# ina.net
KiCad netlist of a schematic drawn in EAGLE
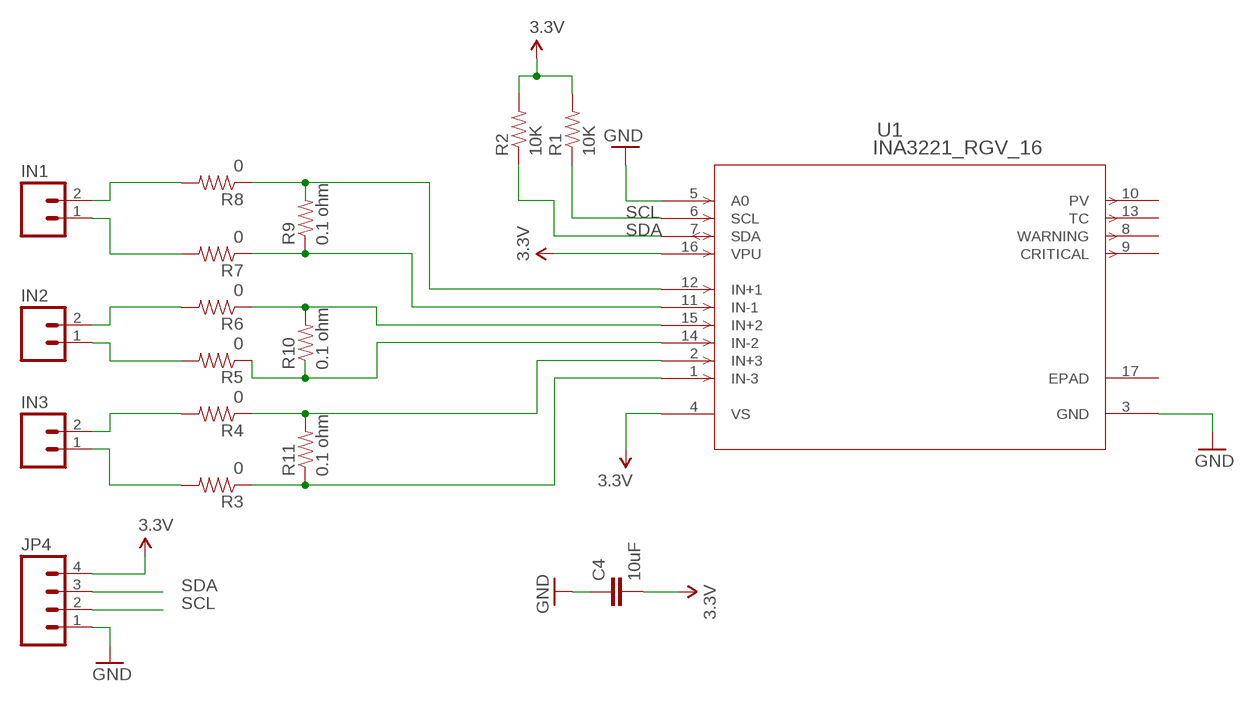
[diagram p0: schematic, sheet 1]

(export (version "E")
  (design (tool "Eeschema 10.0.6"))
  (components
    (comp (ref "C4")
      (value "10uF")
      (footprint "eagle-import:1206")
      (fields (field (name "MF") "WALSIN") (field (name "MPN") "1206B106K160CT"))
      (libsource (lib "eagle-import") (part "CAP1206"))
    )
    (comp (ref "IN1")
      (value "M02PTH")
      (footprint "eagle-import:1X02")
      (libsource (lib "eagle-import") (part "M02PTH"))
    )
    (comp (ref "IN2")
      (value "M02PTH")
      (footprint "eagle-import:1X02")
      (libsource (lib "eagle-import") (part "M02PTH"))
    )
    (comp (ref "IN3")
      (value "M02PTH")
      (footprint "eagle-import:1X02")
      (libsource (lib "eagle-import") (part "M02PTH"))
    )
    (comp (ref "JP4")
      (value "M04LONGPADS")
      (footprint "eagle-import:1X04_LONGPADS")
      (libsource (lib "eagle-import") (part "M04LONGPADS"))
    )
    (comp (ref "R1")
      (value "10K")
      (footprint "eagle-import:1206")
      (fields (field (name "MF") "YAGEO (PHYCOMP)") (field (name "MPN") "RC1206FR-0710KL"))
      (libsource (lib "eagle-import") (part "RESISTOR1206"))
    )
    (comp (ref "R2")
      (value "10K")
      (footprint "eagle-import:1206")
      (fields (field (name "MF") "YAGEO (PHYCOMP)") (field (name "MPN") "RC1206FR-0710KL"))
      (libsource (lib "eagle-import") (part "RESISTOR1206"))
    )
    (comp (ref "R3")
      (value "0")
      (footprint "eagle-import:1206")
      (fields (field (name "MF") "WELWYN") (field (name "MPN") "WCR1206-R005JI"))
      (libsource (lib "eagle-import") (part "RESISTOR1206"))
    )
    (comp (ref "R4")
      (value "0")
      (footprint "eagle-import:1206")
      (fields (field (name "MF") "WELWYN") (field (name "MPN") "WCR1206-R005JI"))
      (libsource (lib "eagle-import") (part "RESISTOR1206"))
    )
    (comp (ref "R5")
      (value "0")
      (footprint "eagle-import:1206")
      (fields (field (name "MF") "WELWYN") (field (name "MPN") "WCR1206-R005JI"))
      (libsource (lib "eagle-import") (part "RESISTOR1206"))
    )
    (comp (ref "R6")
      (value "0")
      (footprint "eagle-import:1206")
      (fields (field (name "MF") "WELWYN") (field (name "MPN") "WCR1206-R005JI"))
      (libsource (lib "eagle-import") (part "RESISTOR1206"))
    )
    (comp (ref "R7")
      (value "0")
      (footprint "eagle-import:1206")
      (fields (field (name "MF") "WELWYN") (field (name "MPN") "WCR1206-R005JI"))
      (libsource (lib "eagle-import") (part "RESISTOR1206"))
    )
    (comp (ref "R8")
      (value "0")
      (footprint "eagle-import:1206")
      (fields (field (name "MF") "WELWYN") (field (name "MPN") "WCR1206-R005JI"))
      (libsource (lib "eagle-import") (part "RESISTOR1206"))
    )
    (comp (ref "R9")
      (value "0.1 ohm")
      (footprint "eagle-import:R2512")
      (fields (field (name "MF") "BOURNS") (field (name "MPN") "CRM2512-JX-R100ELF"))
      (libsource (lib "eagle-import") (part "RESISTOR2512"))
    )
    (comp (ref "R10")
      (value "0.1 ohm")
      (footprint "eagle-import:R2512")
      (fields (field (name "MF") "BOURNS") (field (name "MPN") "CRM2512-JX-R100ELF"))
      (libsource (lib "eagle-import") (part "RESISTOR2512"))
    )
    (comp (ref "R11")
      (value "0.1 ohm")
      (footprint "eagle-import:R2512")
      (fields (field (name "MF") "BOURNS") (field (name "MPN") "CRM2512-JX-R100ELF"))
      (libsource (lib "eagle-import") (part "RESISTOR2512"))
    )
    (comp (ref "U1")
      (value "INA3221_RGV_16")
      (footprint "eagle-import:RGV16_2P16X2P16")
      (fields
        (field (name "GENERIC_PART_NUMBER") "INA3221")
        (field (name "MANUFACTURER") "Texas Instruments")
        (field (name "MF") "TEXAS INSTRUMENTS")
      )
      (libsource (lib "eagle-import") (part "INA3221_RGV_16"))
    )
  )
  (nets
    (net (code "1") (name "/SCL") (class "Default")
      (node (ref "JP4") (pin "2") (pinfunction "2_2") (pintype "passive"))
      (node (ref "R1") (pin "1") (pinfunction "1_1") (pintype "passive"))
      (node (ref "U1") (pin "6") (pinfunction "SCL_6") (pintype "input"))
    )
    (net (code "2") (name "/SDA") (class "Default")
      (node (ref "JP4") (pin "3") (pinfunction "3_3") (pintype "passive"))
      (node (ref "R2") (pin "1") (pinfunction "1_1") (pintype "passive"))
      (node (ref "U1") (pin "7") (pinfunction "SDA_7") (pintype "bidirectional"))
    )
    (net (code "3") (name "3.3V") (class "Default")
      (node (ref "C4") (pin "2") (pinfunction "2_2") (pintype "passive"))
      (node (ref "JP4") (pin "4") (pinfunction "4_4") (pintype "passive"))
      (node (ref "R1") (pin "2") (pinfunction "2_2") (pintype "passive"))
      (node (ref "R2") (pin "2") (pinfunction "2_2") (pintype "passive"))
      (node (ref "U1") (pin "16") (pinfunction "VPU_16") (pintype "input"))
      (node (ref "U1") (pin "4") (pinfunction "VS_4") (pintype "passive"))
    )
    (net (code "4") (name "GND") (class "Default")
      (node (ref "C4") (pin "1") (pinfunction "1_1") (pintype "passive"))
      (node (ref "JP4") (pin "1") (pinfunction "1_1") (pintype "passive"))
      (node (ref "U1") (pin "3") (pinfunction "GND_3") (pintype "power_in"))
      (node (ref "U1") (pin "5") (pinfunction "A0_5") (pintype "input"))
    )
    (net (code "5") (name "Net-(IN1-Pad1)") (class "Default")
      (node (ref "IN1") (pin "1") (pinfunction "1_1") (pintype "passive"))
      (node (ref "R7") (pin "2") (pinfunction "2_2") (pintype "passive"))
    )
    (net (code "6") (name "Net-(IN1-Pad2)") (class "Default")
      (node (ref "IN1") (pin "2") (pinfunction "2_2") (pintype "passive"))
      (node (ref "R8") (pin "2") (pinfunction "2_2") (pintype "passive"))
    )
    (net (code "7") (name "Net-(IN2-Pad1)") (class "Default")
      (node (ref "IN2") (pin "1") (pinfunction "1_1") (pintype "passive"))
      (node (ref "R5") (pin "2") (pinfunction "2_2") (pintype "passive"))
    )
    (net (code "8") (name "Net-(IN2-Pad2)") (class "Default")
      (node (ref "IN2") (pin "2") (pinfunction "2_2") (pintype "passive"))
      (node (ref "R6") (pin "2") (pinfunction "2_2") (pintype "passive"))
    )
    (net (code "9") (name "Net-(IN3-Pad1)") (class "Default")
      (node (ref "IN3") (pin "1") (pinfunction "1_1") (pintype "passive"))
      (node (ref "R3") (pin "2") (pinfunction "2_2") (pintype "passive"))
    )
    (net (code "10") (name "Net-(IN3-Pad2)") (class "Default")
      (node (ref "IN3") (pin "2") (pinfunction "2_2") (pintype "passive"))
      (node (ref "R4") (pin "2") (pinfunction "2_2") (pintype "passive"))
    )
    (net (code "11") (name "Net-(U1-IN+1)") (class "Default")
      (node (ref "R8") (pin "1") (pinfunction "1_1") (pintype "passive"))
      (node (ref "R9") (pin "2") (pinfunction "2_2") (pintype "passive"))
      (node (ref "U1") (pin "12") (pinfunction "IN+1_12") (pintype "input"))
    )
    (net (code "12") (name "Net-(U1-IN+2)") (class "Default")
      (node (ref "R10") (pin "2") (pinfunction "2_2") (pintype "passive"))
      (node (ref "R6") (pin "1") (pinfunction "1_1") (pintype "passive"))
      (node (ref "U1") (pin "15") (pinfunction "IN+2_15") (pintype "input"))
    )
    (net (code "13") (name "Net-(U1-IN+3)") (class "Default")
      (node (ref "R11") (pin "2") (pinfunction "2_2") (pintype "passive"))
      (node (ref "R4") (pin "1") (pinfunction "1_1") (pintype "passive"))
      (node (ref "U1") (pin "2") (pinfunction "IN+3_2") (pintype "input"))
    )
    (net (code "14") (name "Net-(U1-IN-1)") (class "Default")
      (node (ref "R7") (pin "1") (pinfunction "1_1") (pintype "passive"))
      (node (ref "R9") (pin "1") (pinfunction "1_1") (pintype "passive"))
      (node (ref "U1") (pin "11") (pinfunction "IN-1_11") (pintype "input"))
    )
    (net (code "15") (name "Net-(U1-IN-2)") (class "Default")
      (node (ref "R10") (pin "1") (pinfunction "1_1") (pintype "passive"))
      (node (ref "R5") (pin "1") (pinfunction "1_1") (pintype "passive"))
      (node (ref "U1") (pin "14") (pinfunction "IN-2_14") (pintype "input"))
    )
    (net (code "16") (name "Net-(U1-IN-3)") (class "Default")
      (node (ref "R11") (pin "1") (pinfunction "1_1") (pintype "passive"))
      (node (ref "R3") (pin "1") (pinfunction "1_1") (pintype "passive"))
      (node (ref "U1") (pin "1") (pinfunction "IN-3_1") (pintype "input"))
    )
    (net (code "17") (name "unconnected-(U1-CRITICAL-Pad9)") (class "Default")
      (node (ref "U1") (pin "9") (pinfunction "CRITICAL_9") (pintype "output"))
    )
    (net (code "18") (name "unconnected-(U1-EPAD-Pad17)") (class "Default")
      (node (ref "U1") (pin "17") (pinfunction "EPAD_17") (pintype "passive"))
    )
    (net (code "19") (name "unconnected-(U1-PV-Pad10)") (class "Default")
      (node (ref "U1") (pin "10") (pinfunction "PV_10") (pintype "output"))
    )
    (net (code "20") (name "unconnected-(U1-TC-Pad13)") (class "Default")
      (node (ref "U1") (pin "13") (pinfunction "TC_13") (pintype "output"))
    )
    (net (code "21") (name "unconnected-(U1-WARNING-Pad8)") (class "Default")
      (node (ref "U1") (pin "8") (pinfunction "WARNING_8") (pintype "output"))
    )
  )
)
